# LickDetectorSubCkt_IsolatedDiscreteCompo.net
KiCad netlist of a schematic drawn in EAGLE
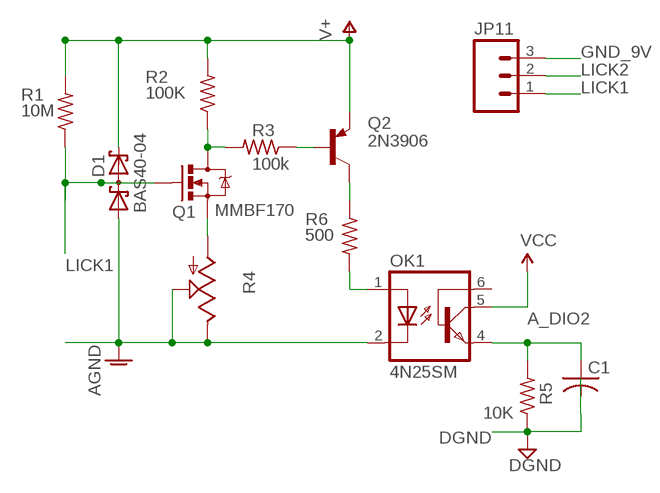
[diagram p0: schematic, sheet 1]

(export (version "E")
  (design (tool "Eeschema 10.0.6"))
  (components
    (comp (ref "C1")
      (value "C-US025-024X044")
      (footprint "eagle-import:C025-024X044")
      (libsource (lib "eagle-import") (part "C-US025-024X044"))
    )
    (comp (ref "D1")
      (value "BAS40-04")
      (footprint "eagle-import:SOT23")
      (libsource (lib "eagle-import") (part "BAS40-04"))
    )
    (comp (ref "JP11")
      (value "M03POLAR")
      (footprint "eagle-import:MOLEX-1X3")
      (libsource (lib "eagle-import") (part "M03POLAR"))
    )
    (comp (ref "OK1")
      (value "4N25SM")
      (footprint "eagle-import:DIL6-SMD")
      (fields (field (name "MF") "FAIRCHILD SEMICONDUCTOR"))
      (libsource (lib "eagle-import") (part "4N?MS25"))
    )
    (comp (ref "Q1")
      (value "MMBF170")
      (footprint "eagle-import:SOT23-3")
      (libsource (lib "eagle-import") (part "MOSFET-NCHANNELAO3404A"))
    )
    (comp (ref "Q2")
      (value "2N3906")
      (footprint "eagle-import:SOT23-BEC")
      (libsource (lib "eagle-import") (part "-PNP-SOT23-BECMMBT3906LT1"))
    )
    (comp (ref "R1")
      (value "10M")
      (footprint "eagle-import:0805S")
      (libsource (lib "eagle-import") (part "RESISTOR_SM0805S"))
    )
    (comp (ref "R2")
      (value "100K")
      (footprint "eagle-import:0805S")
      (libsource (lib "eagle-import") (part "RESISTOR_SM0805S"))
    )
    (comp (ref "R3")
      (value "100k")
      (footprint "eagle-import:0805S")
      (libsource (lib "eagle-import") (part "RESISTOR_SM0805S"))
    )
    (comp (ref "R4")
      (value "TRIM_US-B25P")
      (footprint "eagle-import:B25P")
      (libsource (lib "eagle-import") (part "TRIM_US-B25P"))
    )
    (comp (ref "R5")
      (value "10K")
      (footprint "eagle-import:0805S")
      (libsource (lib "eagle-import") (part "RESISTOR_SM0805S"))
    )
    (comp (ref "R6")
      (value "500")
      (footprint "eagle-import:0805S")
      (libsource (lib "eagle-import") (part "RESISTOR_SM0805S"))
    )
  )
  (nets
    (net (code "1") (name "/A_DIO2") (class "Default")
      (node (ref "C1") (pin "1") (pinfunction "1_1") (pintype "passive"))
      (node (ref "OK1") (pin "4") (pinfunction "EMI_4") (pintype "passive"))
      (node (ref "R5") (pin "2") (pinfunction "2_2") (pintype "passive"))
    )
    (net (code "2") (name "/GND_9V") (class "Default")
      (node (ref "JP11") (pin "3") (pinfunction "3_3") (pintype "passive"))
    )
    (net (code "3") (name "/LICK1") (class "Default")
      (node (ref "D1") (pin "3") (pinfunction "C1A2_3") (pintype "passive"))
      (node (ref "JP11") (pin "1") (pinfunction "1_1") (pintype "passive"))
      (node (ref "Q1") (pin "1") (pinfunction "G_1") (pintype "passive"))
      (node (ref "R1") (pin "1") (pinfunction "1_1") (pintype "passive"))
    )
    (net (code "4") (name "/LICK2") (class "Default")
      (node (ref "JP11") (pin "2") (pinfunction "2_2") (pintype "passive"))
    )
    (net (code "5") (name "AGND") (class "Default")
      (node (ref "D1") (pin "1") (pinfunction "A1_1") (pintype "passive"))
      (node (ref "OK1") (pin "2") (pinfunction "C_2") (pintype "passive"))
      (node (ref "R4") (pin "E") (pinfunction "E_E") (pintype "passive"))
      (node (ref "R4") (pin "S") (pinfunction "S_S") (pintype "passive"))
    )
    (net (code "6") (name "DGND") (class "Default")
      (node (ref "C1") (pin "2") (pinfunction "2_2") (pintype "passive"))
      (node (ref "R5") (pin "1") (pinfunction "1_1") (pintype "passive"))
    )
    (net (code "7") (name "Net-(OK1-A)") (class "Default")
      (node (ref "OK1") (pin "1") (pinfunction "A_1") (pintype "passive"))
      (node (ref "R6") (pin "2") (pinfunction "2_2") (pintype "passive"))
    )
    (net (code "8") (name "Net-(Q1-D)") (class "Default")
      (node (ref "Q1") (pin "3") (pinfunction "D_3") (pintype "passive"))
      (node (ref "R2") (pin "1") (pinfunction "1_1") (pintype "passive"))
      (node (ref "R3") (pin "2") (pinfunction "2_2") (pintype "passive"))
    )
    (net (code "9") (name "Net-(Q1-S)") (class "Default")
      (node (ref "Q1") (pin "2") (pinfunction "S_2") (pintype "passive"))
      (node (ref "R4") (pin "A") (pinfunction "A_A") (pintype "passive"))
    )
    (net (code "10") (name "Net-(Q2-PadB)") (class "Default")
      (node (ref "Q2") (pin "B") (pinfunction "B_B") (pintype "passive"))
      (node (ref "R3") (pin "1") (pinfunction "1_1") (pintype "passive"))
    )
    (net (code "11") (name "Net-(Q2-PadC)") (class "Default")
      (node (ref "Q2") (pin "C") (pinfunction "C_C") (pintype "passive"))
      (node (ref "R6") (pin "1") (pinfunction "1_1") (pintype "passive"))
    )
    (net (code "12") (name "V+") (class "Default")
      (node (ref "D1") (pin "2") (pinfunction "C2_2") (pintype "passive"))
      (node (ref "Q2") (pin "E") (pinfunction "E_E") (pintype "passive"))
      (node (ref "R1") (pin "2") (pinfunction "2_2") (pintype "passive"))
      (node (ref "R2") (pin "2") (pinfunction "2_2") (pintype "passive"))
    )
    (net (code "13") (name "VCC") (class "Default")
      (node (ref "OK1") (pin "5") (pinfunction "COL_5") (pintype "passive"))
    )
    (net (code "14") (name "unconnected-(OK1-BAS-Pad6)") (class "Default")
      (node (ref "OK1") (pin "6") (pinfunction "BAS_6") (pintype "passive"))
    )
  )
)
